# Microduino_v0_5.net
KiCad netlist of a schematic drawn in EAGLE
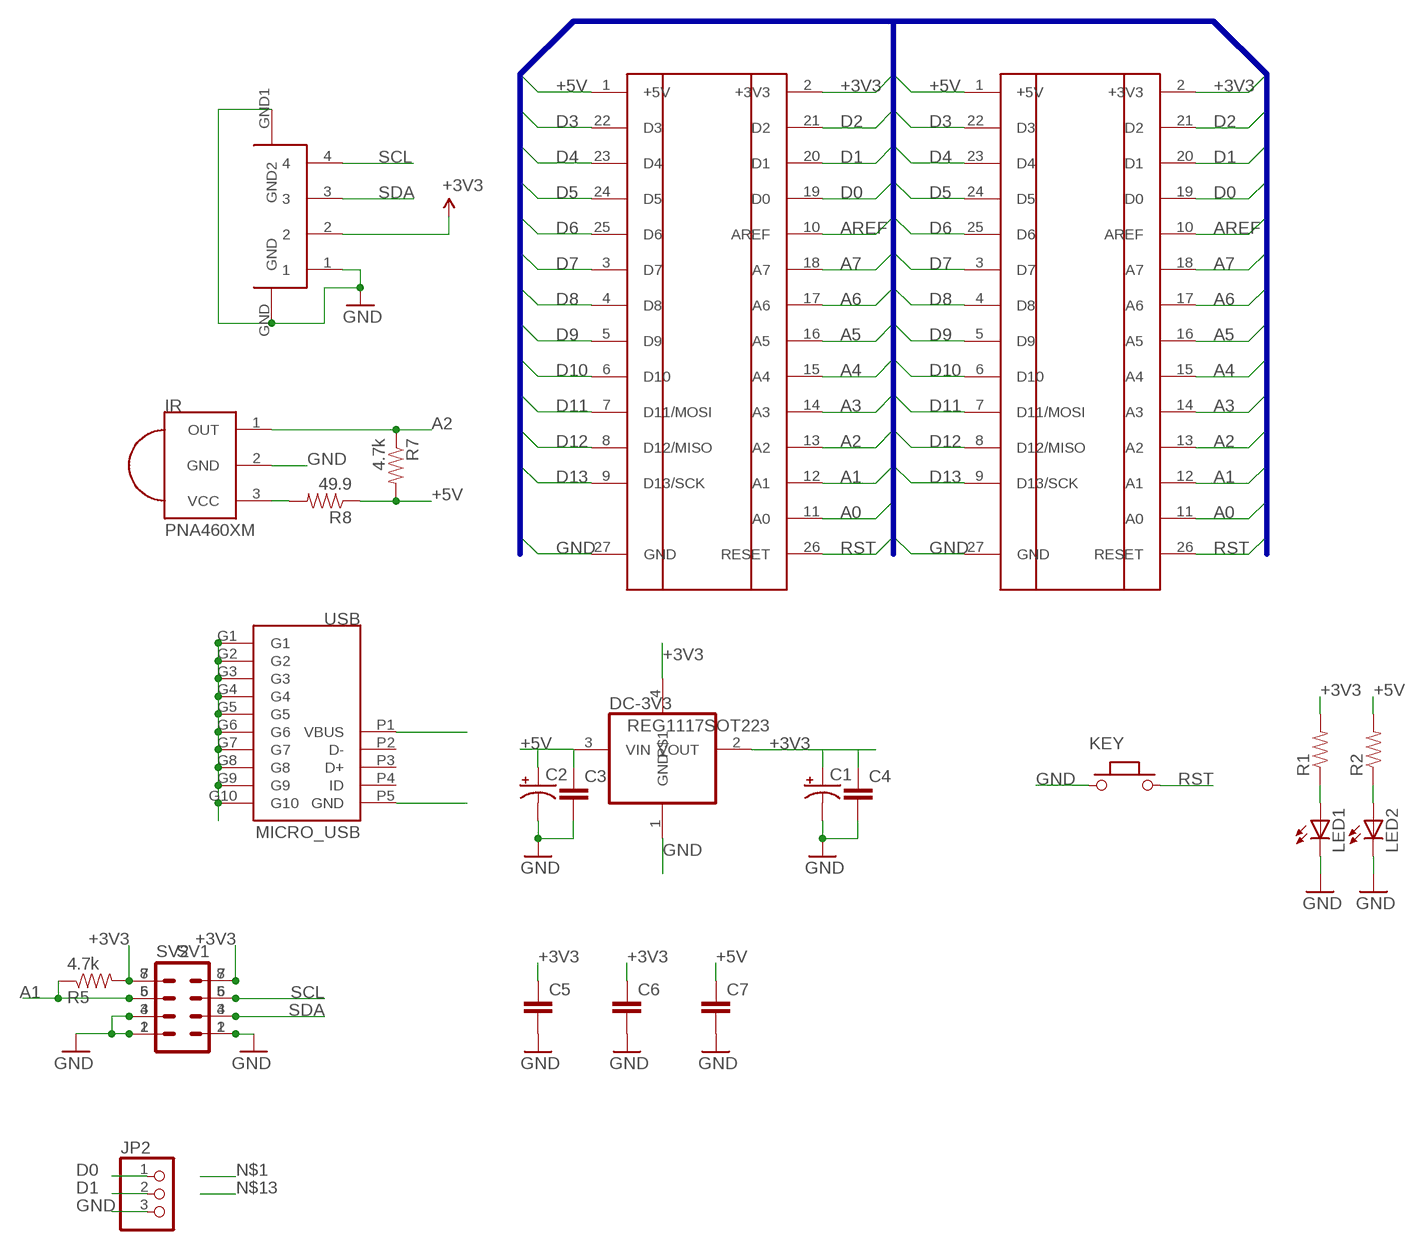
[diagram p0: schematic, sheet 1]

(export (version "E")
  (design (tool "Eeschema 10.0.6"))
  (components
    (comp (ref "C1")
      (value "CAP_POL3528")
      (footprint "eagle-import:EIA3528")
      (libsource (lib "eagle-import") (part "CAP_POL3528"))
    )
    (comp (ref "C2")
      (value "CAP_POL3528")
      (footprint "eagle-import:EIA3528")
      (libsource (lib "eagle-import") (part "CAP_POL3528"))
    )
    (comp (ref "C3")
      (value "CAP0603-CAP")
      (footprint "eagle-import:0603-CAP")
      (libsource (lib "eagle-import") (part "CAP0603-CAP"))
    )
    (comp (ref "C4")
      (value "CAP0603-CAP")
      (footprint "eagle-import:0603-CAP")
      (libsource (lib "eagle-import") (part "CAP0603-CAP"))
    )
    (comp (ref "C5")
      (value "CAP0603-CAP")
      (footprint "eagle-import:0603-CAP")
      (libsource (lib "eagle-import") (part "CAP0603-CAP"))
    )
    (comp (ref "C6")
      (value "CAP0603-CAP")
      (footprint "eagle-import:0603-CAP")
      (libsource (lib "eagle-import") (part "CAP0603-CAP"))
    )
    (comp (ref "C7")
      (value "CAP0603-CAP")
      (footprint "eagle-import:0603-CAP")
      (libsource (lib "eagle-import") (part "CAP0603-CAP"))
    )
    (comp (ref "DC-3V3")
      (value "REG1117SOT223")
      (footprint "eagle-import:SOT223")
      (libsource (lib "eagle-import") (part "REG1117SOT223"))
    )
    (comp (ref "IR")
      (value "PNA460XM")
      (footprint "eagle-import:PNA460XM")
      (libsource (lib "eagle-import") (part "PNA460XM"))
    )
    (comp (ref "JP2")
      (value "PINHD-1X3")
      (footprint "eagle-import:1X03")
      (libsource (lib "eagle-import") (part "PINHD-1X3"))
    )
    (comp (ref "KEY")
      (value "KEY-TES-018")
      (footprint "eagle-import:KEY-TS-018")
      (libsource (lib "eagle-import") (part "KEY-TES-018"))
    )
    (comp (ref "LED1")
      (value "LED0805")
      (footprint "eagle-import:0805-LED")
      (libsource (lib "eagle-import") (part "LED0805"))
    )
    (comp (ref "LED2")
      (value "LED0805")
      (footprint "eagle-import:0805-LED")
      (libsource (lib "eagle-import") (part "LED0805"))
    )
    (comp (ref "R1")
      (value "RESISTOR0603-RES")
      (footprint "eagle-import:0603-RES")
      (libsource (lib "eagle-import") (part "RESISTOR0603-RES"))
    )
    (comp (ref "R2")
      (value "RESISTOR0603-RES")
      (footprint "eagle-import:0603-RES")
      (libsource (lib "eagle-import") (part "RESISTOR0603-RES"))
    )
    (comp (ref "R5")
      (value "4.7k")
      (footprint "eagle-import:0603-RES")
      (libsource (lib "eagle-import") (part "MY_RESISTOR0603-RES"))
    )
    (comp (ref "R7")
      (value "4.7k")
      (footprint "eagle-import:0603-RES")
      (libsource (lib "eagle-import") (part "MY_RESISTOR0603-RES"))
    )
    (comp (ref "R8")
      (value "49.9")
      (footprint "eagle-import:0603-RES")
      (libsource (lib "eagle-import") (part "MY_RESISTOR0603-RES"))
    )
    (comp (ref "SV1")
      (value "MA04-2")
      (footprint "eagle-import:MA04-2")
      (fields (field (name "OC_FARNELL") "unknown") (field (name "OC_NEWARK") "unknown"))
      (libsource (lib "eagle-import") (part "MA04-2"))
    )
    (comp (ref "SV2")
      (value "MA04-2")
      (footprint "eagle-import:MA04-2")
      (fields (field (name "OC_FARNELL") "unknown") (field (name "OC_NEWARK") "unknown"))
      (libsource (lib "eagle-import") (part "MA04-2"))
    )
    (comp (ref "U$1")
      (value "PING-MICRDUINO/1009")
      (footprint "eagle-import:PIN-MICRODUINO-1009")
      (libsource (lib "eagle-import") (part "PING-MICRDUINO/1009"))
    )
    (comp (ref "U$2")
      (value "PING-MICRDUINO/1009")
      (footprint "eagle-import:PIN-MICRODUINO-1009")
      (libsource (lib "eagle-import") (part "PING-MICRDUINO/1009"))
    )
    (comp (ref "U$3")
      (value "S4B-XH-SM4-TB")
      (footprint "eagle-import:XH-SM4-TB")
      (libsource (lib "eagle-import") (part "S4B-XH-SM4-TB"))
    )
    (comp (ref "USB")
      (value "MICRO_USB")
      (footprint "eagle-import:MICRO_USB_LJ")
      (libsource (lib "eagle-import") (part "MICRO_USB"))
    )
  )
  (nets
    (net (code "1") (name "+3V3") (class "Default")
      (node (ref "C1") (pin "A") (pinfunction "+_A") (pintype "passive"))
      (node (ref "C4") (pin "1") (pinfunction "1_1") (pintype "passive"))
      (node (ref "C5") (pin "1") (pinfunction "1_1") (pintype "passive"))
      (node (ref "C6") (pin "1") (pinfunction "1_1") (pintype "passive"))
      (node (ref "DC-3V3") (pin "2") (pinfunction "VOUT_2") (pintype "output"))
      (node (ref "DC-3V3") (pin "4") (pinfunction "P$1_4") (pintype "bidirectional"))
      (node (ref "R1") (pin "2") (pinfunction "2_2") (pintype "passive"))
      (node (ref "R5") (pin "2") (pinfunction "2_2") (pintype "passive"))
      (node (ref "SV1") (pin "7") (pinfunction "7_7") (pintype "passive"))
      (node (ref "SV1") (pin "8") (pinfunction "8_8") (pintype "passive"))
      (node (ref "SV2") (pin "7") (pinfunction "7_7") (pintype "passive"))
      (node (ref "SV2") (pin "8") (pinfunction "8_8") (pintype "passive"))
      (node (ref "U$1") (pin "2") (pinfunction "+3V3_2") (pintype "bidirectional"))
      (node (ref "U$2") (pin "2") (pinfunction "+3V3_2") (pintype "bidirectional"))
      (node (ref "U$3") (pin "2") (pinfunction "2_2") (pintype "bidirectional"))
    )
    (net (code "2") (name "/+5V") (class "Default")
      (node (ref "C2") (pin "A") (pinfunction "+_A") (pintype "passive"))
      (node (ref "C3") (pin "1") (pinfunction "1_1") (pintype "passive"))
      (node (ref "C7") (pin "1") (pinfunction "1_1") (pintype "passive"))
      (node (ref "DC-3V3") (pin "3") (pinfunction "VIN_3") (pintype "input"))
      (node (ref "R2") (pin "2") (pinfunction "2_2") (pintype "passive"))
      (node (ref "R7") (pin "2") (pinfunction "2_2") (pintype "passive"))
      (node (ref "R8") (pin "1") (pinfunction "1_1") (pintype "passive"))
      (node (ref "U$1") (pin "1") (pinfunction "+5V_1") (pintype "bidirectional"))
      (node (ref "U$2") (pin "1") (pinfunction "+5V_1") (pintype "bidirectional"))
      (node (ref "USB") (pin "P1") (pinfunction "VBUS_P1") (pintype "power_in"))
    )
    (net (code "3") (name "/A0") (class "Default")
      (node (ref "U$1") (pin "11") (pinfunction "A0_11") (pintype "bidirectional"))
      (node (ref "U$2") (pin "11") (pinfunction "A0_11") (pintype "bidirectional"))
    )
    (net (code "4") (name "/A1") (class "Default")
      (node (ref "R5") (pin "1") (pinfunction "1_1") (pintype "passive"))
      (node (ref "SV1") (pin "5") (pinfunction "5_5") (pintype "passive"))
      (node (ref "SV2") (pin "6") (pinfunction "6_6") (pintype "passive"))
      (node (ref "U$1") (pin "12") (pinfunction "A1_12") (pintype "bidirectional"))
      (node (ref "U$2") (pin "12") (pinfunction "A1_12") (pintype "bidirectional"))
    )
    (net (code "5") (name "/A2") (class "Default")
      (node (ref "IR") (pin "1") (pinfunction "OUT_1") (pintype "output"))
      (node (ref "R7") (pin "1") (pinfunction "1_1") (pintype "passive"))
      (node (ref "U$1") (pin "13") (pinfunction "A2_13") (pintype "bidirectional"))
      (node (ref "U$2") (pin "13") (pinfunction "A2_13") (pintype "bidirectional"))
    )
    (net (code "6") (name "/A3") (class "Default")
      (node (ref "U$1") (pin "14") (pinfunction "A3_14") (pintype "bidirectional"))
      (node (ref "U$2") (pin "14") (pinfunction "A3_14") (pintype "bidirectional"))
    )
    (net (code "7") (name "/A4") (class "Default")
      (node (ref "U$1") (pin "15") (pinfunction "A4_15") (pintype "bidirectional"))
      (node (ref "U$2") (pin "15") (pinfunction "A4_15") (pintype "bidirectional"))
    )
    (net (code "8") (name "/A5") (class "Default")
      (node (ref "U$1") (pin "16") (pinfunction "A5_16") (pintype "bidirectional"))
      (node (ref "U$2") (pin "16") (pinfunction "A5_16") (pintype "bidirectional"))
    )
    (net (code "9") (name "/A6") (class "Default")
      (node (ref "U$1") (pin "17") (pinfunction "A6_17") (pintype "bidirectional"))
      (node (ref "U$2") (pin "17") (pinfunction "A6_17") (pintype "bidirectional"))
    )
    (net (code "10") (name "/A7") (class "Default")
      (node (ref "U$1") (pin "18") (pinfunction "A7_18") (pintype "bidirectional"))
      (node (ref "U$2") (pin "18") (pinfunction "A7_18") (pintype "bidirectional"))
    )
    (net (code "11") (name "/AREF") (class "Default")
      (node (ref "U$1") (pin "10") (pinfunction "AREF_10") (pintype "bidirectional"))
      (node (ref "U$2") (pin "10") (pinfunction "AREF_10") (pintype "bidirectional"))
    )
    (net (code "12") (name "/D0") (class "Default")
      (node (ref "JP2") (pin "1") (pinfunction "1_1") (pintype "passive"))
      (node (ref "U$1") (pin "19") (pinfunction "D0_19") (pintype "bidirectional"))
      (node (ref "U$2") (pin "19") (pinfunction "D0_19") (pintype "bidirectional"))
    )
    (net (code "13") (name "/D1") (class "Default")
      (node (ref "JP2") (pin "2") (pinfunction "2_2") (pintype "passive"))
      (node (ref "U$1") (pin "20") (pinfunction "D1_20") (pintype "bidirectional"))
      (node (ref "U$2") (pin "20") (pinfunction "D1_20") (pintype "bidirectional"))
    )
    (net (code "14") (name "/D2") (class "Default")
      (node (ref "U$1") (pin "21") (pinfunction "D2_21") (pintype "bidirectional"))
      (node (ref "U$2") (pin "21") (pinfunction "D2_21") (pintype "bidirectional"))
    )
    (net (code "15") (name "/D3") (class "Default")
      (node (ref "U$1") (pin "22") (pinfunction "D3_22") (pintype "bidirectional"))
      (node (ref "U$2") (pin "22") (pinfunction "D3_22") (pintype "bidirectional"))
    )
    (net (code "16") (name "/D4") (class "Default")
      (node (ref "U$1") (pin "23") (pinfunction "D4_23") (pintype "bidirectional"))
      (node (ref "U$2") (pin "23") (pinfunction "D4_23") (pintype "bidirectional"))
    )
    (net (code "17") (name "/D5") (class "Default")
      (node (ref "U$1") (pin "24") (pinfunction "D5_24") (pintype "bidirectional"))
      (node (ref "U$2") (pin "24") (pinfunction "D5_24") (pintype "bidirectional"))
    )
    (net (code "18") (name "/D6") (class "Default")
      (node (ref "U$1") (pin "25") (pinfunction "D6_25") (pintype "bidirectional"))
      (node (ref "U$2") (pin "25") (pinfunction "D6_25") (pintype "bidirectional"))
    )
    (net (code "19") (name "/D7") (class "Default")
      (node (ref "U$1") (pin "3") (pinfunction "D7_3") (pintype "bidirectional"))
      (node (ref "U$2") (pin "3") (pinfunction "D7_3") (pintype "bidirectional"))
    )
    (net (code "20") (name "/D8") (class "Default")
      (node (ref "U$1") (pin "4") (pinfunction "D8_4") (pintype "bidirectional"))
      (node (ref "U$2") (pin "4") (pinfunction "D8_4") (pintype "bidirectional"))
    )
    (net (code "21") (name "/D9") (class "Default")
      (node (ref "U$1") (pin "5") (pinfunction "D9_5") (pintype "bidirectional"))
      (node (ref "U$2") (pin "5") (pinfunction "D9_5") (pintype "bidirectional"))
    )
    (net (code "22") (name "/D10") (class "Default")
      (node (ref "U$1") (pin "6") (pinfunction "D10_6") (pintype "bidirectional"))
      (node (ref "U$2") (pin "6") (pinfunction "D10_6") (pintype "bidirectional"))
    )
    (net (code "23") (name "/D11") (class "Default")
      (node (ref "U$1") (pin "7") (pinfunction "D11/MOSI_7") (pintype "bidirectional"))
      (node (ref "U$2") (pin "7") (pinfunction "D11/MOSI_7") (pintype "bidirectional"))
    )
    (net (code "24") (name "/D12") (class "Default")
      (node (ref "U$1") (pin "8") (pinfunction "D12/MISO_8") (pintype "bidirectional"))
      (node (ref "U$2") (pin "8") (pinfunction "D12/MISO_8") (pintype "bidirectional"))
    )
    (net (code "25") (name "/D13") (class "Default")
      (node (ref "U$1") (pin "9") (pinfunction "D13/SCK_9") (pintype "bidirectional"))
      (node (ref "U$2") (pin "9") (pinfunction "D13/SCK_9") (pintype "bidirectional"))
    )
    (net (code "28") (name "/RST") (class "Default")
      (node (ref "KEY") (pin "1") (pinfunction "2_1") (pintype "bidirectional"))
      (node (ref "U$1") (pin "26") (pinfunction "RESET_26") (pintype "bidirectional"))
      (node (ref "U$2") (pin "26") (pinfunction "RESET_26") (pintype "bidirectional"))
    )
    (net (code "29") (name "/SCL") (class "Default")
      (node (ref "SV1") (pin "6") (pinfunction "6_6") (pintype "passive"))
      (node (ref "SV2") (pin "5") (pinfunction "5_5") (pintype "passive"))
      (node (ref "U$3") (pin "4") (pinfunction "4_4") (pintype "bidirectional"))
    )
    (net (code "30") (name "/SDA") (class "Default")
      (node (ref "SV1") (pin "4") (pinfunction "4_4") (pintype "passive"))
      (node (ref "SV2") (pin "3") (pinfunction "3_3") (pintype "passive"))
      (node (ref "U$3") (pin "3") (pinfunction "3_3") (pintype "bidirectional"))
    )
    (net (code "31") (name "GND") (class "Default")
      (node (ref "C1") (pin "C") (pinfunction "-_C") (pintype "passive"))
      (node (ref "C2") (pin "C") (pinfunction "-_C") (pintype "passive"))
      (node (ref "C3") (pin "2") (pinfunction "2_2") (pintype "passive"))
      (node (ref "C4") (pin "2") (pinfunction "2_2") (pintype "passive"))
      (node (ref "C5") (pin "2") (pinfunction "2_2") (pintype "passive"))
      (node (ref "C6") (pin "2") (pinfunction "2_2") (pintype "passive"))
      (node (ref "C7") (pin "2") (pinfunction "2_2") (pintype "passive"))
      (node (ref "DC-3V3") (pin "1") (pinfunction "GND_1") (pintype "power_in"))
      (node (ref "IR") (pin "2") (pinfunction "GND_2") (pintype "power_in"))
      (node (ref "JP2") (pin "3") (pinfunction "3_3") (pintype "passive"))
      (node (ref "KEY") (pin "2") (pinfunction "1_2") (pintype "bidirectional"))
      (node (ref "LED1") (pin "C") (pinfunction "C_C") (pintype "passive"))
      (node (ref "LED2") (pin "C") (pinfunction "C_C") (pintype "passive"))
      (node (ref "SV1") (pin "1") (pinfunction "1_1") (pintype "passive"))
      (node (ref "SV1") (pin "2") (pinfunction "2_2") (pintype "passive"))
      (node (ref "SV1") (pin "3") (pinfunction "3_3") (pintype "passive"))
      (node (ref "SV2") (pin "1") (pinfunction "1_1") (pintype "passive"))
      (node (ref "SV2") (pin "2") (pinfunction "2_2") (pintype "passive"))
      (node (ref "SV2") (pin "4") (pinfunction "4_4") (pintype "passive"))
      (node (ref "U$1") (pin "27") (pinfunction "GND_27") (pintype "bidirectional"))
      (node (ref "U$2") (pin "27") (pinfunction "GND_27") (pintype "bidirectional"))
      (node (ref "U$3") (pin "1") (pinfunction "1_1") (pintype "bidirectional"))
      (node (ref "U$3") (pin "GND") (pinfunction "GND_GND") (pintype "bidirectional"))
      (node (ref "U$3") (pin "GND1") (pinfunction "GND2_GND1") (pintype "bidirectional"))
      (node (ref "USB") (pin "G1") (pinfunction "G1_G1") (pintype "bidirectional"))
      (node (ref "USB") (pin "G10") (pinfunction "G10_G10") (pintype "passive"))
      (node (ref "USB") (pin "G2") (pinfunction "G2_G2") (pintype "bidirectional"))
      (node (ref "USB") (pin "G3") (pinfunction "G3_G3") (pintype "bidirectional"))
      (node (ref "USB") (pin "G4") (pinfunction "G4_G4") (pintype "bidirectional"))
      (node (ref "USB") (pin "G5") (pinfunction "G5_G5") (pintype "bidirectional"))
      (node (ref "USB") (pin "G6") (pinfunction "G6_G6") (pintype "bidirectional"))
      (node (ref "USB") (pin "G7") (pinfunction "G7_G7") (pintype "passive"))
      (node (ref "USB") (pin "G8") (pinfunction "G8_G8") (pintype "passive"))
      (node (ref "USB") (pin "G9") (pinfunction "G9_G9") (pintype "passive"))
      (node (ref "USB") (pin "P5") (pinfunction "GND_P5") (pintype "passive"))
    )
    (net (code "32") (name "Net-(IR-VCC)") (class "Default")
      (node (ref "IR") (pin "3") (pinfunction "VCC_3") (pintype "power_in"))
      (node (ref "R8") (pin "2") (pinfunction "2_2") (pintype "passive"))
    )
    (net (code "33") (name "Net-(LED1-PadA)") (class "Default")
      (node (ref "LED1") (pin "A") (pinfunction "A_A") (pintype "passive"))
      (node (ref "R1") (pin "1") (pinfunction "1_1") (pintype "passive"))
    )
    (net (code "34") (name "Net-(LED2-PadA)") (class "Default")
      (node (ref "LED2") (pin "A") (pinfunction "A_A") (pintype "passive"))
      (node (ref "R2") (pin "1") (pinfunction "1_1") (pintype "passive"))
    )
    (net (code "35") (name "unconnected-(USB-D+-PadP3)") (class "Default")
      (node (ref "USB") (pin "P3") (pinfunction "D+_P3") (pintype "bidirectional"))
    )
    (net (code "36") (name "unconnected-(USB-D--PadP2)") (class "Default")
      (node (ref "USB") (pin "P2") (pinfunction "D-_P2") (pintype "bidirectional"))
    )
    (net (code "37") (name "unconnected-(USB-ID-PadP4)") (class "Default")
      (node (ref "USB") (pin "P4") (pinfunction "ID_P4") (pintype "bidirectional"))
    )
  )
)
